# EP1K100QC208-2.net
KiCad netlist of a schematic drawn in Altium Designer
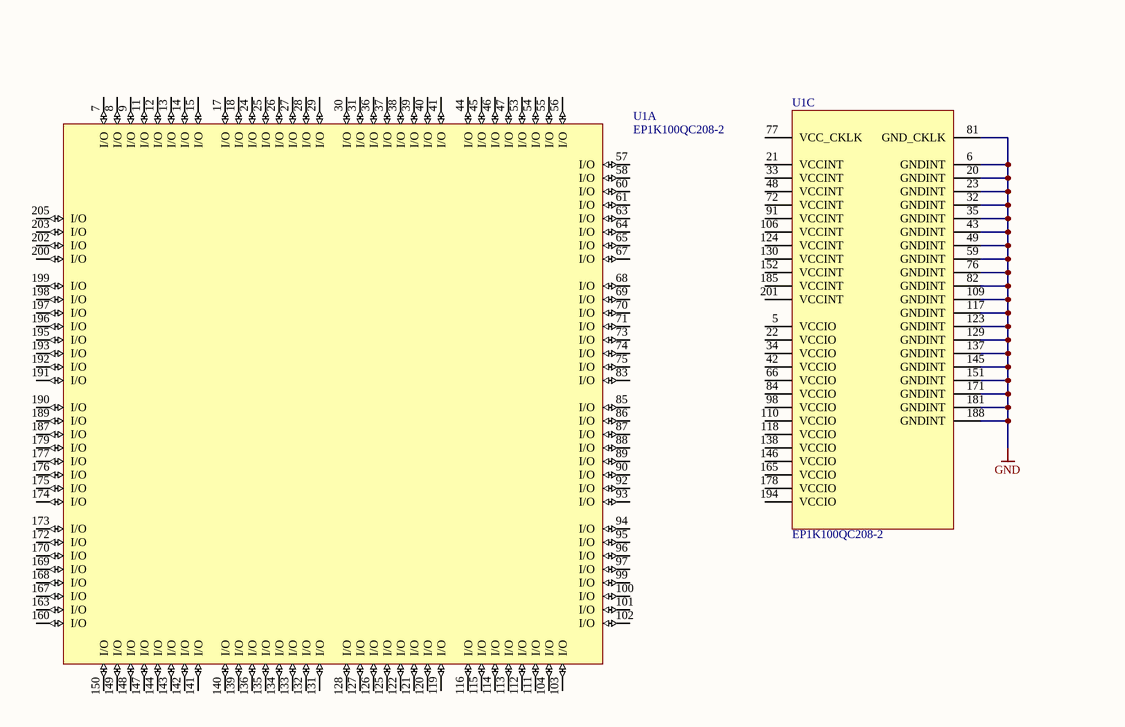
[diagram p0: EP1K100QC208-2.SchDoc, left]
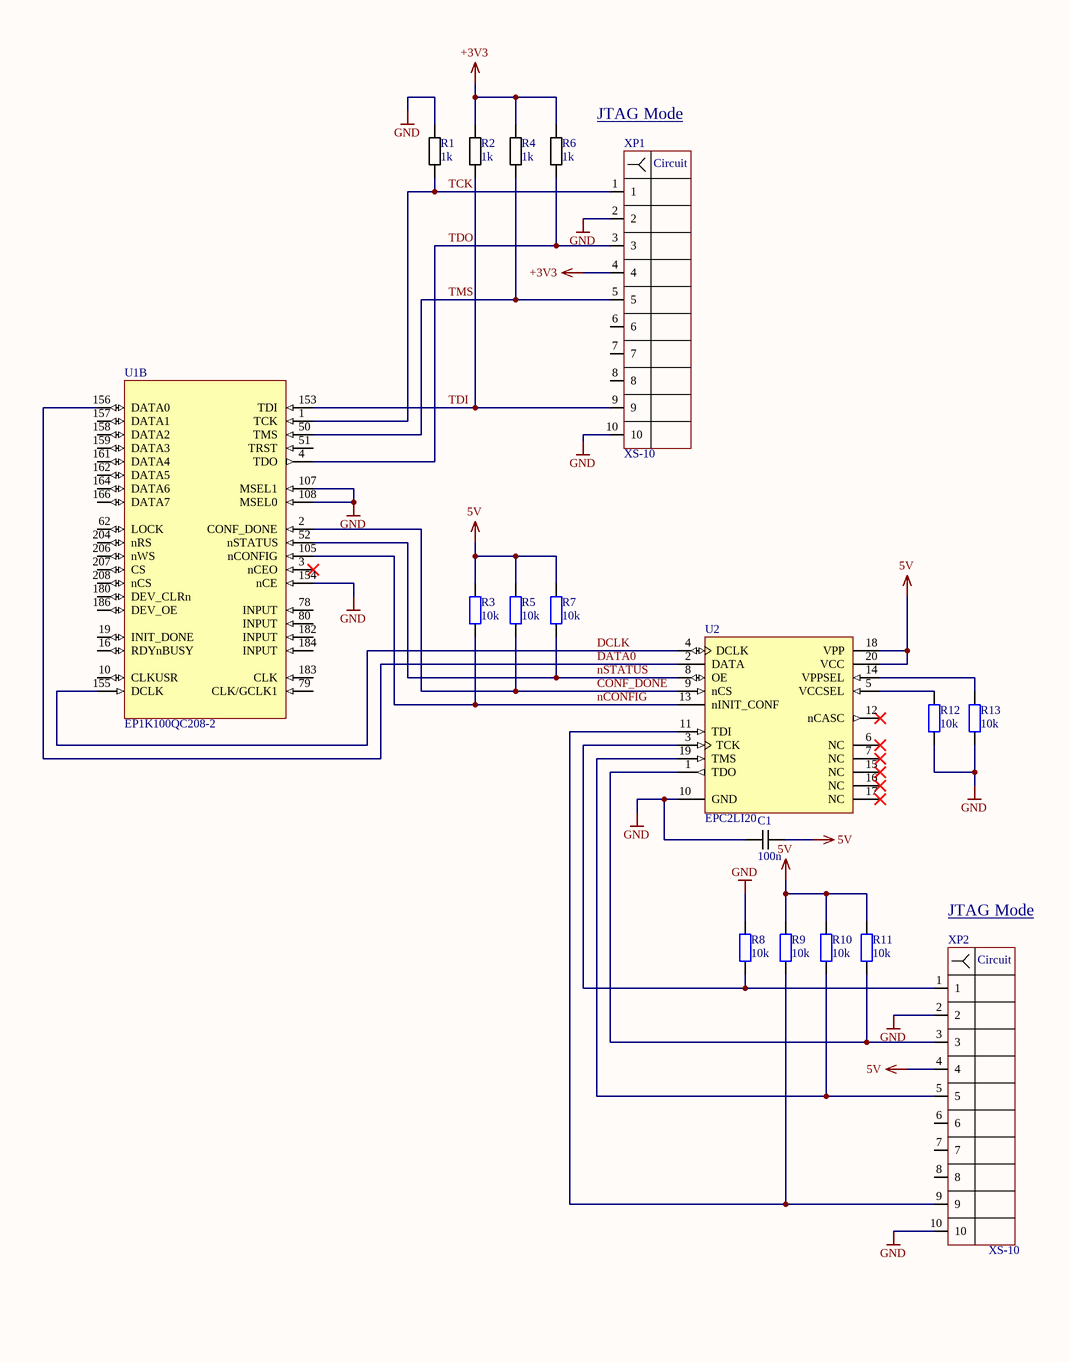
[diagram p1: EP1K100QC208-2.SchDoc, right]

(export (version "E")
  (design (tool "Eeschema 10.0.6"))
  (components
    (comp (ref "C1")
      (value "100n")
      (footprint "CAPC1608(0603)N")
      (description "?")
      (fields (field (name "PART NUMBER") "CAPC1608(0603)"))
      (libsource (lib "SssAccesDatbase") (part "Cap"))
    )
    (comp (ref "R1")
      (value "1k")
      (footprint "RESC1608(0603)N")
      (fields (field (name "PART NUMBER") "RESC1608(0603)") (field (name "DIGI-KEY PART NUMBER") "???"))
      (libsource (lib "SssAccesDatbaseDYandex") (part "Resistor general"))
    )
    (comp (ref "R2")
      (value "1k")
      (footprint "RESC1608(0603)N")
      (fields (field (name "PART NUMBER") "RESC1608(0603)") (field (name "DIGI-KEY PART NUMBER") "???"))
      (libsource (lib "SssAccesDatbaseDYandex") (part "Resistor general"))
    )
    (comp (ref "R3")
      (value "10k")
      (footprint "RESC1608(0603)N")
      (description "Resistor")
      (fields (field (name "PART NUMBER") "RESC1608(0603)") (field (name "DIGI-KEY PART NUMBER") "???"))
      (libsource (lib "ADdatabaseLibfile") (part "Res2"))
    )
    (comp (ref "R4")
      (value "1k")
      (footprint "RESC1608(0603)N")
      (fields (field (name "PART NUMBER") "RESC1608(0603)") (field (name "DIGI-KEY PART NUMBER") "???"))
      (libsource (lib "SssAccesDatbaseDYandex") (part "Resistor general"))
    )
    (comp (ref "R5")
      (value "10k")
      (footprint "RESC1608(0603)N")
      (description "Resistor")
      (fields (field (name "PART NUMBER") "RESC1608(0603)") (field (name "DIGI-KEY PART NUMBER") "???"))
      (libsource (lib "ADdatabaseLibfile") (part "Res2"))
    )
    (comp (ref "R6")
      (value "1k")
      (footprint "RESC1608(0603)N")
      (fields (field (name "PART NUMBER") "RESC1608(0603)") (field (name "DIGI-KEY PART NUMBER") "???"))
      (libsource (lib "SssAccesDatbaseDYandex") (part "Resistor general"))
    )
    (comp (ref "R7")
      (value "10k")
      (footprint "RESC1608(0603)N")
      (description "Resistor")
      (fields (field (name "PART NUMBER") "RESC1608(0603)") (field (name "DIGI-KEY PART NUMBER") "???"))
      (libsource (lib "ADdatabaseLibfile") (part "Res2"))
    )
    (comp (ref "R8")
      (value "10k")
      (footprint "RESC1608(0603)N")
      (description "Resistor")
      (fields (field (name "PART NUMBER") "RESC1608(0603)") (field (name "DIGI-KEY PART NUMBER") "???"))
      (libsource (lib "") (part "Res2_1"))
    )
    (comp (ref "R9")
      (value "10k")
      (footprint "RESC1608(0603)N")
      (description "Resistor")
      (fields (field (name "PART NUMBER") "RESC1608(0603)") (field (name "DIGI-KEY PART NUMBER") "???"))
      (libsource (lib "ADdatabaseLibfile") (part "Res2"))
    )
    (comp (ref "R10")
      (value "10k")
      (footprint "RESC1608(0603)N")
      (description "Resistor")
      (fields (field (name "PART NUMBER") "RESC1608(0603)") (field (name "DIGI-KEY PART NUMBER") "???"))
      (libsource (lib "ADdatabaseLibfile") (part "Res2"))
    )
    (comp (ref "R11")
      (value "10k")
      (footprint "RESC1608(0603)N")
      (description "Resistor")
      (fields (field (name "PART NUMBER") "RESC1608(0603)") (field (name "DIGI-KEY PART NUMBER") "???"))
      (libsource (lib "ADdatabaseLibfile") (part "Res2"))
    )
    (comp (ref "R12")
      (value "10k")
      (footprint "RESC1608(0603)N")
      (description "Resistor")
      (fields (field (name "PART NUMBER") "RESC1608(0603)") (field (name "DIGI-KEY PART NUMBER") "???"))
      (libsource (lib "ADdatabaseLibfile") (part "Res2"))
    )
    (comp (ref "R13")
      (value "10k")
      (footprint "RESC1608(0603)N")
      (description "Resistor")
      (fields (field (name "PART NUMBER") "RESC1608(0603)") (field (name "DIGI-KEY PART NUMBER") "???"))
      (libsource (lib "ADdatabaseLibfile") (part "Res2"))
    )
    (comp (ref "U1")
      (value "EP1K100QC208-2")
      (footprint "PQFP208_N")
      (fields (field (name "PUBLISHER") "Altium Limited"))
      (libsource (lib "") (part "EP1K100QC208-2_1"))
    )
    (comp (ref "U2")
      (value "EPC2LI20")
      (footprint "PLCC20_L")
      (description "IC - Ser. Config Mem Flash 1.6Mb 10 MHz")
      (fields (field (name "PUBLISHER") "Altium Limited"))
      (libsource (lib "ADdatabaseLibfile") (part "EPC2LI20"))
    )
    (comp (ref "XP1")
      (value "XS-10")
      (footprint "BH-10")
      (fields
        (field (name "PART NUMBER") "3220-10-0100-00")
        (field (name "DIGI-KEY PART NUMBER") "1175-1627-ND")
      )
      (libsource (lib "ADdatabaseLibfile") (part "XS-10"))
    )
    (comp (ref "XP2")
      (value "XS-10")
      (footprint "BH-10")
      (fields (field (name "PART NUMBER") "BH-10"))
      (libsource (lib "ADdatabaseLibfile") (part "XS-10"))
    )
  )
  (nets
    (net (code "1") (name "+3V3") (class "Default")
      (node (ref "R2") (pin "2") (pinfunction "2_2") (pintype "passive"))
      (node (ref "R4") (pin "2") (pinfunction "2_2") (pintype "passive"))
      (node (ref "R6") (pin "2") (pinfunction "2_2") (pintype "passive"))
      (node (ref "XP1") (pin "4") (pinfunction "4_4") (pintype "passive"))
    )
    (net (code "2") (name "/CONF_DONE") (class "Default")
      (node (ref "R5") (pin "2") (pinfunction "2_2") (pintype "passive"))
      (node (ref "U1") (pin "2") (pinfunction "CONF_DONE_2") (pintype "input"))
      (node (ref "U2") (pin "9") (pinfunction "nCS_9") (pintype "input"))
    )
    (net (code "3") (name "/DATA0") (class "Default")
      (node (ref "U1") (pin "156") (pinfunction "DATA0_156") (pintype "bidirectional"))
      (node (ref "U2") (pin "2") (pinfunction "DATA_2") (pintype "tri_state"))
    )
    (net (code "4") (name "/DCLK") (class "Default")
      (node (ref "U1") (pin "155") (pinfunction "DCLK_155") (pintype "input"))
      (node (ref "U2") (pin "4") (pinfunction "DCLK_4") (pintype "bidirectional"))
    )
    (net (code "5") (name "/TCK") (class "Default")
      (node (ref "R1") (pin "1") (pinfunction "1_1") (pintype "passive"))
      (node (ref "U1") (pin "1") (pinfunction "TCK_1") (pintype "input"))
      (node (ref "XP1") (pin "1") (pinfunction "1_1") (pintype "passive"))
    )
    (net (code "6") (name "/TDI") (class "Default")
      (node (ref "R2") (pin "1") (pinfunction "1_1") (pintype "passive"))
      (node (ref "U1") (pin "153") (pinfunction "TDI_153") (pintype "input"))
      (node (ref "XP1") (pin "9") (pinfunction "9_9") (pintype "passive"))
    )
    (net (code "7") (name "/TDO") (class "Default")
      (node (ref "R6") (pin "1") (pinfunction "1_1") (pintype "passive"))
      (node (ref "U1") (pin "4") (pinfunction "TDO_4") (pintype "output"))
      (node (ref "XP1") (pin "3") (pinfunction "3_3") (pintype "passive"))
    )
    (net (code "8") (name "/TMS") (class "Default")
      (node (ref "R4") (pin "1") (pinfunction "1_1") (pintype "passive"))
      (node (ref "U1") (pin "50") (pinfunction "TMS_50") (pintype "input"))
      (node (ref "XP1") (pin "5") (pinfunction "5_5") (pintype "passive"))
    )
    (net (code "9") (name "/nCONFIG") (class "Default")
      (node (ref "R3") (pin "2") (pinfunction "2_2") (pintype "passive"))
      (node (ref "U1") (pin "105") (pinfunction "nCONFIG_105") (pintype "input"))
      (node (ref "U2") (pin "13") (pinfunction "nINIT_CONF_13") (pintype "open_collector"))
    )
    (net (code "10") (name "/nSTATUS") (class "Default")
      (node (ref "R7") (pin "2") (pinfunction "2_2") (pintype "passive"))
      (node (ref "U1") (pin "52") (pinfunction "nSTATUS_52") (pintype "input"))
      (node (ref "U2") (pin "8") (pinfunction "OE_8") (pintype "bidirectional"))
    )
    (net (code "11") (name "5V") (class "Default")
      (node (ref "C1") (pin "2") (pinfunction "2_2") (pintype "passive"))
      (node (ref "R10") (pin "1") (pinfunction "1_1") (pintype "passive"))
      (node (ref "R11") (pin "1") (pinfunction "1_1") (pintype "passive"))
      (node (ref "R3") (pin "1") (pinfunction "1_1") (pintype "passive"))
      (node (ref "R5") (pin "1") (pinfunction "1_1") (pintype "passive"))
      (node (ref "R7") (pin "1") (pinfunction "1_1") (pintype "passive"))
      (node (ref "R9") (pin "1") (pinfunction "1_1") (pintype "passive"))
      (node (ref "U2") (pin "18") (pinfunction "VPP_18") (pintype "power_in"))
      (node (ref "U2") (pin "20") (pinfunction "VCC_20") (pintype "power_in"))
      (node (ref "XP2") (pin "4") (pinfunction "4_4") (pintype "passive"))
    )
    (net (code "12") (name "GND") (class "Default")
      (node (ref "C1") (pin "1") (pinfunction "1_1") (pintype "passive"))
      (node (ref "R1") (pin "2") (pinfunction "2_2") (pintype "passive"))
      (node (ref "R12") (pin "2") (pinfunction "2_2") (pintype "passive"))
      (node (ref "R13") (pin "2") (pinfunction "2_2") (pintype "passive"))
      (node (ref "R8") (pin "2") (pinfunction "2_2") (pintype "passive"))
      (node (ref "U1") (pin "107") (pinfunction "MSEL1_107") (pintype "input"))
      (node (ref "U1") (pin "108") (pinfunction "MSEL0_108") (pintype "input"))
      (node (ref "U1") (pin "109") (pinfunction "GNDINT_109") (pintype "power_in"))
      (node (ref "U1") (pin "117") (pinfunction "GNDINT_117") (pintype "power_in"))
      (node (ref "U1") (pin "123") (pinfunction "GNDINT_123") (pintype "power_in"))
      (node (ref "U1") (pin "129") (pinfunction "GNDINT_129") (pintype "power_in"))
      (node (ref "U1") (pin "137") (pinfunction "GNDINT_137") (pintype "power_in"))
      (node (ref "U1") (pin "145") (pinfunction "GNDINT_145") (pintype "power_in"))
      (node (ref "U1") (pin "151") (pinfunction "GNDINT_151") (pintype "power_in"))
      (node (ref "U1") (pin "154") (pinfunction "nCE_154") (pintype "input"))
      (node (ref "U1") (pin "171") (pinfunction "GNDINT_171") (pintype "power_in"))
      (node (ref "U1") (pin "181") (pinfunction "GNDINT_181") (pintype "power_in"))
      (node (ref "U1") (pin "188") (pinfunction "GNDINT_188") (pintype "power_in"))
      (node (ref "U1") (pin "20") (pinfunction "GNDINT_20") (pintype "power_in"))
      (node (ref "U1") (pin "23") (pinfunction "GNDINT_23") (pintype "power_in"))
      (node (ref "U1") (pin "32") (pinfunction "GNDINT_32") (pintype "power_in"))
      (node (ref "U1") (pin "35") (pinfunction "GNDINT_35") (pintype "power_in"))
      (node (ref "U1") (pin "43") (pinfunction "GNDINT_43") (pintype "power_in"))
      (node (ref "U1") (pin "49") (pinfunction "GNDINT_49") (pintype "power_in"))
      (node (ref "U1") (pin "59") (pinfunction "GNDINT_59") (pintype "power_in"))
      (node (ref "U1") (pin "6") (pinfunction "GNDINT_6") (pintype "power_in"))
      (node (ref "U1") (pin "76") (pinfunction "GNDINT_76") (pintype "power_in"))
      (node (ref "U1") (pin "81") (pinfunction "GND_CKLK_81") (pintype "power_in"))
      (node (ref "U1") (pin "82") (pinfunction "GNDINT_82") (pintype "power_in"))
      (node (ref "U2") (pin "10") (pinfunction "GND_10") (pintype "power_in"))
      (node (ref "XP1") (pin "10") (pinfunction "10_10") (pintype "passive"))
      (node (ref "XP1") (pin "2") (pinfunction "2_2") (pintype "passive"))
      (node (ref "XP2") (pin "10") (pinfunction "10_10") (pintype "passive"))
      (node (ref "XP2") (pin "2") (pinfunction "2_2") (pintype "passive"))
    )
    (net (code "13") (name "Net-(U2-TCK)") (class "Default")
      (node (ref "R8") (pin "1") (pinfunction "1_1") (pintype "passive"))
      (node (ref "U2") (pin "3") (pinfunction "TCK_3") (pintype "input"))
      (node (ref "XP2") (pin "1") (pinfunction "1_1") (pintype "passive"))
    )
    (net (code "14") (name "Net-(U2-TDI)") (class "Default")
      (node (ref "R9") (pin "2") (pinfunction "2_2") (pintype "passive"))
      (node (ref "U2") (pin "11") (pinfunction "TDI_11") (pintype "input"))
      (node (ref "XP2") (pin "9") (pinfunction "9_9") (pintype "passive"))
    )
    (net (code "15") (name "Net-(U2-TDO)") (class "Default")
      (node (ref "R11") (pin "2") (pinfunction "2_2") (pintype "passive"))
      (node (ref "U2") (pin "1") (pinfunction "TDO_1") (pintype "output"))
      (node (ref "XP2") (pin "3") (pinfunction "3_3") (pintype "passive"))
    )
    (net (code "16") (name "Net-(U2-TMS)") (class "Default")
      (node (ref "R10") (pin "2") (pinfunction "2_2") (pintype "passive"))
      (node (ref "U2") (pin "19") (pinfunction "TMS_19") (pintype "input"))
      (node (ref "XP2") (pin "5") (pinfunction "5_5") (pintype "passive"))
    )
    (net (code "17") (name "Net-(U2-VCCSEL)") (class "Default")
      (node (ref "R12") (pin "1") (pinfunction "1_1") (pintype "passive"))
      (node (ref "U2") (pin "5") (pinfunction "VCCSEL_5") (pintype "input"))
    )
    (net (code "18") (name "Net-(U2-VPPSEL)") (class "Default")
      (node (ref "R13") (pin "1") (pinfunction "1_1") (pintype "passive"))
      (node (ref "U2") (pin "14") (pinfunction "VPPSEL_14") (pintype "input"))
    )
    (net (code "19") (name "unconnected-(U1A-I{slash}O-Pad7)") (class "Default")
      (node (ref "U1") (pin "7") (pinfunction "I/O_7") (pintype "bidirectional"))
    )
    (net (code "20") (name "unconnected-(U1A-I{slash}O-Pad8)") (class "Default")
      (node (ref "U1") (pin "8") (pinfunction "I/O_8") (pintype "bidirectional"))
    )
    (net (code "21") (name "unconnected-(U1A-I{slash}O-Pad9)") (class "Default")
      (node (ref "U1") (pin "9") (pinfunction "I/O_9") (pintype "bidirectional"))
    )
    (net (code "22") (name "unconnected-(U1A-I{slash}O-Pad11)") (class "Default")
      (node (ref "U1") (pin "11") (pinfunction "I/O_11") (pintype "bidirectional"))
    )
    (net (code "23") (name "unconnected-(U1A-I{slash}O-Pad12)") (class "Default")
      (node (ref "U1") (pin "12") (pinfunction "I/O_12") (pintype "bidirectional"))
    )
    (net (code "24") (name "unconnected-(U1A-I{slash}O-Pad13)") (class "Default")
      (node (ref "U1") (pin "13") (pinfunction "I/O_13") (pintype "bidirectional"))
    )
    (net (code "25") (name "unconnected-(U1A-I{slash}O-Pad14)") (class "Default")
      (node (ref "U1") (pin "14") (pinfunction "I/O_14") (pintype "bidirectional"))
    )
    (net (code "26") (name "unconnected-(U1A-I{slash}O-Pad15)") (class "Default")
      (node (ref "U1") (pin "15") (pinfunction "I/O_15") (pintype "bidirectional"))
    )
    (net (code "27") (name "unconnected-(U1A-I{slash}O-Pad17)") (class "Default")
      (node (ref "U1") (pin "17") (pinfunction "I/O_17") (pintype "bidirectional"))
    )
    (net (code "28") (name "unconnected-(U1A-I{slash}O-Pad18)") (class "Default")
      (node (ref "U1") (pin "18") (pinfunction "I/O_18") (pintype "bidirectional"))
    )
    (net (code "29") (name "unconnected-(U1A-I{slash}O-Pad24)") (class "Default")
      (node (ref "U1") (pin "24") (pinfunction "I/O_24") (pintype "bidirectional"))
    )
    (net (code "30") (name "unconnected-(U1A-I{slash}O-Pad25)") (class "Default")
      (node (ref "U1") (pin "25") (pinfunction "I/O_25") (pintype "bidirectional"))
    )
    (net (code "31") (name "unconnected-(U1A-I{slash}O-Pad26)") (class "Default")
      (node (ref "U1") (pin "26") (pinfunction "I/O_26") (pintype "bidirectional"))
    )
    (net (code "32") (name "unconnected-(U1A-I{slash}O-Pad27)") (class "Default")
      (node (ref "U1") (pin "27") (pinfunction "I/O_27") (pintype "bidirectional"))
    )
    (net (code "33") (name "unconnected-(U1A-I{slash}O-Pad28)") (class "Default")
      (node (ref "U1") (pin "28") (pinfunction "I/O_28") (pintype "bidirectional"))
    )
    (net (code "34") (name "unconnected-(U1A-I{slash}O-Pad29)") (class "Default")
      (node (ref "U1") (pin "29") (pinfunction "I/O_29") (pintype "bidirectional"))
    )
    (net (code "35") (name "unconnected-(U1A-I{slash}O-Pad30)") (class "Default")
      (node (ref "U1") (pin "30") (pinfunction "I/O_30") (pintype "bidirectional"))
    )
    (net (code "36") (name "unconnected-(U1A-I{slash}O-Pad31)") (class "Default")
      (node (ref "U1") (pin "31") (pinfunction "I/O_31") (pintype "bidirectional"))
    )
    (net (code "37") (name "unconnected-(U1A-I{slash}O-Pad36)") (class "Default")
      (node (ref "U1") (pin "36") (pinfunction "I/O_36") (pintype "bidirectional"))
    )
    (net (code "38") (name "unconnected-(U1A-I{slash}O-Pad37)") (class "Default")
      (node (ref "U1") (pin "37") (pinfunction "I/O_37") (pintype "bidirectional"))
    )
    (net (code "39") (name "unconnected-(U1A-I{slash}O-Pad38)") (class "Default")
      (node (ref "U1") (pin "38") (pinfunction "I/O_38") (pintype "bidirectional"))
    )
    (net (code "40") (name "unconnected-(U1A-I{slash}O-Pad39)") (class "Default")
      (node (ref "U1") (pin "39") (pinfunction "I/O_39") (pintype "bidirectional"))
    )
    (net (code "41") (name "unconnected-(U1A-I{slash}O-Pad40)") (class "Default")
      (node (ref "U1") (pin "40") (pinfunction "I/O_40") (pintype "bidirectional"))
    )
    (net (code "42") (name "unconnected-(U1A-I{slash}O-Pad41)") (class "Default")
      (node (ref "U1") (pin "41") (pinfunction "I/O_41") (pintype "bidirectional"))
    )
    (net (code "43") (name "unconnected-(U1A-I{slash}O-Pad44)") (class "Default")
      (node (ref "U1") (pin "44") (pinfunction "I/O_44") (pintype "bidirectional"))
    )
    (net (code "44") (name "unconnected-(U1A-I{slash}O-Pad45)") (class "Default")
      (node (ref "U1") (pin "45") (pinfunction "I/O_45") (pintype "bidirectional"))
    )
    (net (code "45") (name "unconnected-(U1A-I{slash}O-Pad46)") (class "Default")
      (node (ref "U1") (pin "46") (pinfunction "I/O_46") (pintype "bidirectional"))
    )
    (net (code "46") (name "unconnected-(U1A-I{slash}O-Pad47)") (class "Default")
      (node (ref "U1") (pin "47") (pinfunction "I/O_47") (pintype "bidirectional"))
    )
    (net (code "47") (name "unconnected-(U1A-I{slash}O-Pad53)") (class "Default")
      (node (ref "U1") (pin "53") (pinfunction "I/O_53") (pintype "bidirectional"))
    )
    (net (code "48") (name "unconnected-(U1A-I{slash}O-Pad54)") (class "Default")
      (node (ref "U1") (pin "54") (pinfunction "I/O_54") (pintype "bidirectional"))
    )
    (net (code "49") (name "unconnected-(U1A-I{slash}O-Pad55)") (class "Default")
      (node (ref "U1") (pin "55") (pinfunction "I/O_55") (pintype "bidirectional"))
    )
    (net (code "50") (name "unconnected-(U1A-I{slash}O-Pad56)") (class "Default")
      (node (ref "U1") (pin "56") (pinfunction "I/O_56") (pintype "bidirectional"))
    )
    (net (code "51") (name "unconnected-(U1A-I{slash}O-Pad57)") (class "Default")
      (node (ref "U1") (pin "57") (pinfunction "I/O_57") (pintype "bidirectional"))
    )
    (net (code "52") (name "unconnected-(U1A-I{slash}O-Pad58)") (class "Default")
      (node (ref "U1") (pin "58") (pinfunction "I/O_58") (pintype "bidirectional"))
    )
    (net (code "53") (name "unconnected-(U1A-I{slash}O-Pad60)") (class "Default")
      (node (ref "U1") (pin "60") (pinfunction "I/O_60") (pintype "bidirectional"))
    )
    (net (code "54") (name "unconnected-(U1A-I{slash}O-Pad61)") (class "Default")
      (node (ref "U1") (pin "61") (pinfunction "I/O_61") (pintype "bidirectional"))
    )
    (net (code "55") (name "unconnected-(U1A-I{slash}O-Pad63)") (class "Default")
      (node (ref "U1") (pin "63") (pinfunction "I/O_63") (pintype "bidirectional"))
    )
    (net (code "56") (name "unconnected-(U1A-I{slash}O-Pad64)") (class "Default")
      (node (ref "U1") (pin "64") (pinfunction "I/O_64") (pintype "bidirectional"))
    )
    (net (code "57") (name "unconnected-(U1A-I{slash}O-Pad65)") (class "Default")
      (node (ref "U1") (pin "65") (pinfunction "I/O_65") (pintype "bidirectional"))
    )
    (net (code "58") (name "unconnected-(U1A-I{slash}O-Pad67)") (class "Default")
      (node (ref "U1") (pin "67") (pinfunction "I/O_67") (pintype "bidirectional"))
    )
    (net (code "59") (name "unconnected-(U1A-I{slash}O-Pad68)") (class "Default")
      (node (ref "U1") (pin "68") (pinfunction "I/O_68") (pintype "bidirectional"))
    )
    (net (code "60") (name "unconnected-(U1A-I{slash}O-Pad69)") (class "Default")
      (node (ref "U1") (pin "69") (pinfunction "I/O_69") (pintype "bidirectional"))
    )
    (net (code "61") (name "unconnected-(U1A-I{slash}O-Pad70)") (class "Default")
      (node (ref "U1") (pin "70") (pinfunction "I/O_70") (pintype "bidirectional"))
    )
    (net (code "62") (name "unconnected-(U1A-I{slash}O-Pad71)") (class "Default")
      (node (ref "U1") (pin "71") (pinfunction "I/O_71") (pintype "bidirectional"))
    )
    (net (code "63") (name "unconnected-(U1A-I{slash}O-Pad73)") (class "Default")
      (node (ref "U1") (pin "73") (pinfunction "I/O_73") (pintype "bidirectional"))
    )
    (net (code "64") (name "unconnected-(U1A-I{slash}O-Pad74)") (class "Default")
      (node (ref "U1") (pin "74") (pinfunction "I/O_74") (pintype "bidirectional"))
    )
    (net (code "65") (name "unconnected-(U1A-I{slash}O-Pad75)") (class "Default")
      (node (ref "U1") (pin "75") (pinfunction "I/O_75") (pintype "bidirectional"))
    )
    (net (code "66") (name "unconnected-(U1A-I{slash}O-Pad83)") (class "Default")
      (node (ref "U1") (pin "83") (pinfunction "I/O_83") (pintype "bidirectional"))
    )
    (net (code "67") (name "unconnected-(U1A-I{slash}O-Pad85)") (class "Default")
      (node (ref "U1") (pin "85") (pinfunction "I/O_85") (pintype "bidirectional"))
    )
    (net (code "68") (name "unconnected-(U1A-I{slash}O-Pad86)") (class "Default")
      (node (ref "U1") (pin "86") (pinfunction "I/O_86") (pintype "bidirectional"))
    )
    (net (code "69") (name "unconnected-(U1A-I{slash}O-Pad87)") (class "Default")
      (node (ref "U1") (pin "87") (pinfunction "I/O_87") (pintype "bidirectional"))
    )
    (net (code "70") (name "unconnected-(U1A-I{slash}O-Pad88)") (class "Default")
      (node (ref "U1") (pin "88") (pinfunction "I/O_88") (pintype "bidirectional"))
    )
    (net (code "71") (name "unconnected-(U1A-I{slash}O-Pad89)") (class "Default")
      (node (ref "U1") (pin "89") (pinfunction "I/O_89") (pintype "bidirectional"))
    )
    (net (code "72") (name "unconnected-(U1A-I{slash}O-Pad90)") (class "Default")
      (node (ref "U1") (pin "90") (pinfunction "I/O_90") (pintype "bidirectional"))
    )
    (net (code "73") (name "unconnected-(U1A-I{slash}O-Pad92)") (class "Default")
      (node (ref "U1") (pin "92") (pinfunction "I/O_92") (pintype "bidirectional"))
    )
    (net (code "74") (name "unconnected-(U1A-I{slash}O-Pad93)") (class "Default")
      (node (ref "U1") (pin "93") (pinfunction "I/O_93") (pintype "bidirectional"))
    )
    (net (code "75") (name "unconnected-(U1A-I{slash}O-Pad94)") (class "Default")
      (node (ref "U1") (pin "94") (pinfunction "I/O_94") (pintype "bidirectional"))
    )
    (net (code "76") (name "unconnected-(U1A-I{slash}O-Pad95)") (class "Default")
      (node (ref "U1") (pin "95") (pinfunction "I/O_95") (pintype "bidirectional"))
    )
    (net (code "77") (name "unconnected-(U1A-I{slash}O-Pad96)") (class "Default")
      (node (ref "U1") (pin "96") (pinfunction "I/O_96") (pintype "bidirectional"))
    )
    (net (code "78") (name "unconnected-(U1A-I{slash}O-Pad97)") (class "Default")
      (node (ref "U1") (pin "97") (pinfunction "I/O_97") (pintype "bidirectional"))
    )
    (net (code "79") (name "unconnected-(U1A-I{slash}O-Pad99)") (class "Default")
      (node (ref "U1") (pin "99") (pinfunction "I/O_99") (pintype "bidirectional"))
    )
    (net (code "80") (name "unconnected-(U1A-I{slash}O-Pad100)") (class "Default")
      (node (ref "U1") (pin "100") (pinfunction "I/O_100") (pintype "bidirectional"))
    )
    (net (code "81") (name "unconnected-(U1A-I{slash}O-Pad101)") (class "Default")
      (node (ref "U1") (pin "101") (pinfunction "I/O_101") (pintype "bidirectional"))
    )
    (net (code "82") (name "unconnected-(U1A-I{slash}O-Pad102)") (class "Default")
      (node (ref "U1") (pin "102") (pinfunction "I/O_102") (pintype "bidirectional"))
    )
    (net (code "83") (name "unconnected-(U1A-I{slash}O-Pad103)") (class "Default")
      (node (ref "U1") (pin "103") (pinfunction "I/O_103") (pintype "bidirectional"))
    )
    (net (code "84") (name "unconnected-(U1A-I{slash}O-Pad104)") (class "Default")
      (node (ref "U1") (pin "104") (pinfunction "I/O_104") (pintype "bidirectional"))
    )
    (net (code "85") (name "unconnected-(U1A-I{slash}O-Pad111)") (class "Default")
      (node (ref "U1") (pin "111") (pinfunction "I/O_111") (pintype "bidirectional"))
    )
    (net (code "86") (name "unconnected-(U1A-I{slash}O-Pad112)") (class "Default")
      (node (ref "U1") (pin "112") (pinfunction "I/O_112") (pintype "bidirectional"))
    )
    (net (code "87") (name "unconnected-(U1A-I{slash}O-Pad113)") (class "Default")
      (node (ref "U1") (pin "113") (pinfunction "I/O_113") (pintype "bidirectional"))
    )
    (net (code "88") (name "unconnected-(U1A-I{slash}O-Pad114)") (class "Default")
      (node (ref "U1") (pin "114") (pinfunction "I/O_114") (pintype "bidirectional"))
    )
    (net (code "89") (name "unconnected-(U1A-I{slash}O-Pad115)") (class "Default")
      (node (ref "U1") (pin "115") (pinfunction "I/O_115") (pintype "bidirectional"))
    )
    (net (code "90") (name "unconnected-(U1A-I{slash}O-Pad116)") (class "Default")
      (node (ref "U1") (pin "116") (pinfunction "I/O_116") (pintype "bidirectional"))
    )
    (net (code "91") (name "unconnected-(U1A-I{slash}O-Pad119)") (class "Default")
      (node (ref "U1") (pin "119") (pinfunction "I/O_119") (pintype "bidirectional"))
    )
    (net (code "92") (name "unconnected-(U1A-I{slash}O-Pad120)") (class "Default")
      (node (ref "U1") (pin "120") (pinfunction "I/O_120") (pintype "bidirectional"))
    )
    (net (code "93") (name "unconnected-(U1A-I{slash}O-Pad121)") (class "Default")
      (node (ref "U1") (pin "121") (pinfunction "I/O_121") (pintype "bidirectional"))
    )
    (net (code "94") (name "unconnected-(U1A-I{slash}O-Pad122)") (class "Default")
      (node (ref "U1") (pin "122") (pinfunction "I/O_122") (pintype "bidirectional"))
    )
    (net (code "95") (name "unconnected-(U1A-I{slash}O-Pad125)") (class "Default")
      (node (ref "U1") (pin "125") (pinfunction "I/O_125") (pintype "bidirectional"))
    )
    (net (code "96") (name "unconnected-(U1A-I{slash}O-Pad126)") (class "Default")
      (node (ref "U1") (pin "126") (pinfunction "I/O_126") (pintype "bidirectional"))
    )
    (net (code "97") (name "unconnected-(U1A-I{slash}O-Pad127)") (class "Default")
      (node (ref "U1") (pin "127") (pinfunction "I/O_127") (pintype "bidirectional"))
    )
    (net (code "98") (name "unconnected-(U1A-I{slash}O-Pad128)") (class "Default")
      (node (ref "U1") (pin "128") (pinfunction "I/O_128") (pintype "bidirectional"))
    )
    (net (code "99") (name "unconnected-(U1A-I{slash}O-Pad131)") (class "Default")
      (node (ref "U1") (pin "131") (pinfunction "I/O_131") (pintype "bidirectional"))
    )
    (net (code "100") (name "unconnected-(U1A-I{slash}O-Pad132)") (class "Default")
      (node (ref "U1") (pin "132") (pinfunction "I/O_132") (pintype "bidirectional"))
    )
    (net (code "101") (name "unconnected-(U1A-I{slash}O-Pad133)") (class "Default")
      (node (ref "U1") (pin "133") (pinfunction "I/O_133") (pintype "bidirectional"))
    )
    (net (code "102") (name "unconnected-(U1A-I{slash}O-Pad134)") (class "Default")
      (node (ref "U1") (pin "134") (pinfunction "I/O_134") (pintype "bidirectional"))
    )
    (net (code "103") (name "unconnected-(U1A-I{slash}O-Pad135)") (class "Default")
      (node (ref "U1") (pin "135") (pinfunction "I/O_135") (pintype "bidirectional"))
    )
    (net (code "104") (name "unconnected-(U1A-I{slash}O-Pad136)") (class "Default")
      (node (ref "U1") (pin "136") (pinfunction "I/O_136") (pintype "bidirectional"))
    )
    (net (code "105") (name "unconnected-(U1A-I{slash}O-Pad139)") (class "Default")
      (node (ref "U1") (pin "139") (pinfunction "I/O_139") (pintype "bidirectional"))
    )
    (net (code "106") (name "unconnected-(U1A-I{slash}O-Pad140)") (class "Default")
      (node (ref "U1") (pin "140") (pinfunction "I/O_140") (pintype "bidirectional"))
    )
    (net (code "107") (name "unconnected-(U1A-I{slash}O-Pad141)") (class "Default")
      (node (ref "U1") (pin "141") (pinfunction "I/O_141") (pintype "bidirectional"))
    )
    (net (code "108") (name "unconnected-(U1A-I{slash}O-Pad142)") (class "Default")
      (node (ref "U1") (pin "142") (pinfunction "I/O_142") (pintype "bidirectional"))
    )
    (net (code "109") (name "unconnected-(U1A-I{slash}O-Pad143)") (class "Default")
      (node (ref "U1") (pin "143") (pinfunction "I/O_143") (pintype "bidirectional"))
    )
    (net (code "110") (name "unconnected-(U1A-I{slash}O-Pad144)") (class "Default")
      (node (ref "U1") (pin "144") (pinfunction "I/O_144") (pintype "bidirectional"))
    )
    (net (code "111") (name "unconnected-(U1A-I{slash}O-Pad147)") (class "Default")
      (node (ref "U1") (pin "147") (pinfunction "I/O_147") (pintype "bidirectional"))
    )
    (net (code "112") (name "unconnected-(U1A-I{slash}O-Pad148)") (class "Default")
      (node (ref "U1") (pin "148") (pinfunction "I/O_148") (pintype "bidirectional"))
    )
    (net (code "113") (name "unconnected-(U1A-I{slash}O-Pad149)") (class "Default")
      (node (ref "U1") (pin "149") (pinfunction "I/O_149") (pintype "bidirectional"))
    )
    (net (code "114") (name "unconnected-(U1A-I{slash}O-Pad150)") (class "Default")
      (node (ref "U1") (pin "150") (pinfunction "I/O_150") (pintype "bidirectional"))
    )
    (net (code "115") (name "unconnected-(U1A-I{slash}O-Pad160)") (class "Default")
      (node (ref "U1") (pin "160") (pinfunction "I/O_160") (pintype "bidirectional"))
    )
    (net (code "116") (name "unconnected-(U1A-I{slash}O-Pad163)") (class "Default")
      (node (ref "U1") (pin "163") (pinfunction "I/O_163") (pintype "bidirectional"))
    )
    (net (code "117") (name "unconnected-(U1A-I{slash}O-Pad167)") (class "Default")
      (node (ref "U1") (pin "167") (pinfunction "I/O_167") (pintype "bidirectional"))
    )
    (net (code "118") (name "unconnected-(U1A-I{slash}O-Pad168)") (class "Default")
      (node (ref "U1") (pin "168") (pinfunction "I/O_168") (pintype "bidirectional"))
    )
    (net (code "119") (name "unconnected-(U1A-I{slash}O-Pad169)") (class "Default")
      (node (ref "U1") (pin "169") (pinfunction "I/O_169") (pintype "bidirectional"))
    )
    (net (code "120") (name "unconnected-(U1A-I{slash}O-Pad170)") (class "Default")
      (node (ref "U1") (pin "170") (pinfunction "I/O_170") (pintype "bidirectional"))
    )
    (net (code "121") (name "unconnected-(U1A-I{slash}O-Pad172)") (class "Default")
      (node (ref "U1") (pin "172") (pinfunction "I/O_172") (pintype "bidirectional"))
    )
    (net (code "122") (name "unconnected-(U1A-I{slash}O-Pad173)") (class "Default")
      (node (ref "U1") (pin "173") (pinfunction "I/O_173") (pintype "bidirectional"))
    )
    (net (code "123") (name "unconnected-(U1A-I{slash}O-Pad174)") (class "Default")
      (node (ref "U1") (pin "174") (pinfunction "I/O_174") (pintype "bidirectional"))
    )
    (net (code "124") (name "unconnected-(U1A-I{slash}O-Pad175)") (class "Default")
      (node (ref "U1") (pin "175") (pinfunction "I/O_175") (pintype "bidirectional"))
    )
    (net (code "125") (name "unconnected-(U1A-I{slash}O-Pad176)") (class "Default")
      (node (ref "U1") (pin "176") (pinfunction "I/O_176") (pintype "bidirectional"))
    )
    (net (code "126") (name "unconnected-(U1A-I{slash}O-Pad177)") (class "Default")
      (node (ref "U1") (pin "177") (pinfunction "I/O_177") (pintype "bidirectional"))
    )
    (net (code "127") (name "unconnected-(U1A-I{slash}O-Pad179)") (class "Default")
      (node (ref "U1") (pin "179") (pinfunction "I/O_179") (pintype "bidirectional"))
    )
    (net (code "128") (name "unconnected-(U1A-I{slash}O-Pad187)") (class "Default")
      (node (ref "U1") (pin "187") (pinfunction "I/O_187") (pintype "bidirectional"))
    )
    (net (code "129") (name "unconnected-(U1A-I{slash}O-Pad189)") (class "Default")
      (node (ref "U1") (pin "189") (pinfunction "I/O_189") (pintype "bidirectional"))
    )
    (net (code "130") (name "unconnected-(U1A-I{slash}O-Pad190)") (class "Default")
      (node (ref "U1") (pin "190") (pinfunction "I/O_190") (pintype "bidirectional"))
    )
    (net (code "131") (name "unconnected-(U1A-I{slash}O-Pad191)") (class "Default")
      (node (ref "U1") (pin "191") (pinfunction "I/O_191") (pintype "bidirectional"))
    )
    (net (code "132") (name "unconnected-(U1A-I{slash}O-Pad192)") (class "Default")
      (node (ref "U1") (pin "192") (pinfunction "I/O_192") (pintype "bidirectional"))
    )
    (net (code "133") (name "unconnected-(U1A-I{slash}O-Pad193)") (class "Default")
      (node (ref "U1") (pin "193") (pinfunction "I/O_193") (pintype "bidirectional"))
    )
    (net (code "134") (name "unconnected-(U1A-I{slash}O-Pad195)") (class "Default")
      (node (ref "U1") (pin "195") (pinfunction "I/O_195") (pintype "bidirectional"))
    )
    (net (code "135") (name "unconnected-(U1A-I{slash}O-Pad196)") (class "Default")
      (node (ref "U1") (pin "196") (pinfunction "I/O_196") (pintype "bidirectional"))
    )
    (net (code "136") (name "unconnected-(U1A-I{slash}O-Pad197)") (class "Default")
      (node (ref "U1") (pin "197") (pinfunction "I/O_197") (pintype "bidirectional"))
    )
    (net (code "137") (name "unconnected-(U1A-I{slash}O-Pad198)") (class "Default")
      (node (ref "U1") (pin "198") (pinfunction "I/O_198") (pintype "bidirectional"))
    )
    (net (code "138") (name "unconnected-(U1A-I{slash}O-Pad199)") (class "Default")
      (node (ref "U1") (pin "199") (pinfunction "I/O_199") (pintype "bidirectional"))
    )
    (net (code "139") (name "unconnected-(U1A-I{slash}O-Pad200)") (class "Default")
      (node (ref "U1") (pin "200") (pinfunction "I/O_200") (pintype "bidirectional"))
    )
    (net (code "140") (name "unconnected-(U1A-I{slash}O-Pad202)") (class "Default")
      (node (ref "U1") (pin "202") (pinfunction "I/O_202") (pintype "bidirectional"))
    )
    (net (code "141") (name "unconnected-(U1A-I{slash}O-Pad203)") (class "Default")
      (node (ref "U1") (pin "203") (pinfunction "I/O_203") (pintype "bidirectional"))
    )
    (net (code "142") (name "unconnected-(U1A-I{slash}O-Pad205)") (class "Default")
      (node (ref "U1") (pin "205") (pinfunction "I/O_205") (pintype "bidirectional"))
    )
    (net (code "143") (name "unconnected-(U1B-CLK-Pad183)") (class "Default")
      (node (ref "U1") (pin "183") (pinfunction "CLK_183") (pintype "input"))
    )
    (net (code "144") (name "unconnected-(U1B-CLKUSR-Pad10)") (class "Default")
      (node (ref "U1") (pin "10") (pinfunction "CLKUSR_10") (pintype "bidirectional"))
    )
    (net (code "145") (name "unconnected-(U1B-CLK{slash}GCLK1-Pad79)") (class "Default")
      (node (ref "U1") (pin "79") (pinfunction "CLK/GCLK1_79") (pintype "input"))
    )
    (net (code "146") (name "unconnected-(U1B-CS-Pad207)") (class "Default")
      (node (ref "U1") (pin "207") (pinfunction "CS_207") (pintype "bidirectional"))
    )
    (net (code "147") (name "unconnected-(U1B-DATA1-Pad157)") (class "Default")
      (node (ref "U1") (pin "157") (pinfunction "DATA1_157") (pintype "bidirectional"))
    )
    (net (code "148") (name "unconnected-(U1B-DATA2-Pad158)") (class "Default")
      (node (ref "U1") (pin "158") (pinfunction "DATA2_158") (pintype "bidirectional"))
    )
    (net (code "149") (name "unconnected-(U1B-DATA3-Pad159)") (class "Default")
      (node (ref "U1") (pin "159") (pinfunction "DATA3_159") (pintype "bidirectional"))
    )
    (net (code "150") (name "unconnected-(U1B-DATA4-Pad161)") (class "Default")
      (node (ref "U1") (pin "161") (pinfunction "DATA4_161") (pintype "bidirectional"))
    )
    (net (code "151") (name "unconnected-(U1B-DATA5-Pad162)") (class "Default")
      (node (ref "U1") (pin "162") (pinfunction "DATA5_162") (pintype "bidirectional"))
    )
    (net (code "152") (name "unconnected-(U1B-DATA6-Pad164)") (class "Default")
      (node (ref "U1") (pin "164") (pinfunction "DATA6_164") (pintype "bidirectional"))
    )
    (net (code "153") (name "unconnected-(U1B-DATA7-Pad166)") (class "Default")
      (node (ref "U1") (pin "166") (pinfunction "DATA7_166") (pintype "bidirectional"))
    )
    (net (code "154") (name "unconnected-(U1B-DEV_CLRn-Pad180)") (class "Default")
      (node (ref "U1") (pin "180") (pinfunction "DEV_CLRn_180") (pintype "bidirectional"))
    )
    (net (code "155") (name "unconnected-(U1B-DEV_OE-Pad186)") (class "Default")
      (node (ref "U1") (pin "186") (pinfunction "DEV_OE_186") (pintype "bidirectional"))
    )
    (net (code "156") (name "unconnected-(U1B-INIT_DONE-Pad19)") (class "Default")
      (node (ref "U1") (pin "19") (pinfunction "INIT_DONE_19") (pintype "bidirectional"))
    )
    (net (code "157") (name "unconnected-(U1B-INPUT-Pad78)") (class "Default")
      (node (ref "U1") (pin "78") (pinfunction "INPUT_78") (pintype "input"))
    )
    (net (code "158") (name "unconnected-(U1B-INPUT-Pad80)") (class "Default")
      (node (ref "U1") (pin "80") (pinfunction "INPUT_80") (pintype "input"))
    )
    (net (code "159") (name "unconnected-(U1B-INPUT-Pad182)") (class "Default")
      (node (ref "U1") (pin "182") (pinfunction "INPUT_182") (pintype "input"))
    )
    (net (code "160") (name "unconnected-(U1B-INPUT-Pad184)") (class "Default")
      (node (ref "U1") (pin "184") (pinfunction "INPUT_184") (pintype "input"))
    )
    (net (code "161") (name "unconnected-(U1B-LOCK-Pad62)") (class "Default")
      (node (ref "U1") (pin "62") (pinfunction "LOCK_62") (pintype "bidirectional"))
    )
    (net (code "162") (name "unconnected-(U1B-RDYnBUSY-Pad16)") (class "Default")
      (node (ref "U1") (pin "16") (pinfunction "RDYnBUSY_16") (pintype "bidirectional"))
    )
    (net (code "163") (name "unconnected-(U1B-TRST-Pad51)") (class "Default")
      (node (ref "U1") (pin "51") (pinfunction "TRST_51") (pintype "input"))
    )
    (net (code "164") (name "unconnected-(U1B-nCEO-Pad3)") (class "Default")
      (node (ref "U1") (pin "3") (pinfunction "nCEO_3") (pintype "input+no_connect"))
    )
    (net (code "165") (name "unconnected-(U1B-nCS-Pad208)") (class "Default")
      (node (ref "U1") (pin "208") (pinfunction "nCS_208") (pintype "bidirectional"))
    )
    (net (code "166") (name "unconnected-(U1B-nRS-Pad204)") (class "Default")
      (node (ref "U1") (pin "204") (pinfunction "nRS_204") (pintype "bidirectional"))
    )
    (net (code "167") (name "unconnected-(U1B-nWS-Pad206)") (class "Default")
      (node (ref "U1") (pin "206") (pinfunction "nWS_206") (pintype "bidirectional"))
    )
    (net (code "168") (name "unconnected-(U1C-VCCINT-Pad21)") (class "Default")
      (node (ref "U1") (pin "21") (pinfunction "VCCINT_21") (pintype "power_in"))
    )
    (net (code "169") (name "unconnected-(U1C-VCCINT-Pad33)") (class "Default")
      (node (ref "U1") (pin "33") (pinfunction "VCCINT_33") (pintype "power_in"))
    )
    (net (code "170") (name "unconnected-(U1C-VCCINT-Pad48)") (class "Default")
      (node (ref "U1") (pin "48") (pinfunction "VCCINT_48") (pintype "power_in"))
    )
    (net (code "171") (name "unconnected-(U1C-VCCINT-Pad72)") (class "Default")
      (node (ref "U1") (pin "72") (pinfunction "VCCINT_72") (pintype "power_in"))
    )
    (net (code "172") (name "unconnected-(U1C-VCCINT-Pad91)") (class "Default")
      (node (ref "U1") (pin "91") (pinfunction "VCCINT_91") (pintype "power_in"))
    )
    (net (code "173") (name "unconnected-(U1C-VCCINT-Pad106)") (class "Default")
      (node (ref "U1") (pin "106") (pinfunction "VCCINT_106") (pintype "power_in"))
    )
    (net (code "174") (name "unconnected-(U1C-VCCINT-Pad124)") (class "Default")
      (node (ref "U1") (pin "124") (pinfunction "VCCINT_124") (pintype "power_in"))
    )
    (net (code "175") (name "unconnected-(U1C-VCCINT-Pad130)") (class "Default")
      (node (ref "U1") (pin "130") (pinfunction "VCCINT_130") (pintype "power_in"))
    )
    (net (code "176") (name "unconnected-(U1C-VCCINT-Pad152)") (class "Default")
      (node (ref "U1") (pin "152") (pinfunction "VCCINT_152") (pintype "power_in"))
    )
    (net (code "177") (name "unconnected-(U1C-VCCINT-Pad185)") (class "Default")
      (node (ref "U1") (pin "185") (pinfunction "VCCINT_185") (pintype "power_in"))
    )
    (net (code "178") (name "unconnected-(U1C-VCCINT-Pad201)") (class "Default")
      (node (ref "U1") (pin "201") (pinfunction "VCCINT_201") (pintype "power_in"))
    )
    (net (code "179") (name "unconnected-(U1C-VCCIO-Pad5)") (class "Default")
      (node (ref "U1") (pin "5") (pinfunction "VCCIO_5") (pintype "power_in"))
    )
    (net (code "180") (name "unconnected-(U1C-VCCIO-Pad22)") (class "Default")
      (node (ref "U1") (pin "22") (pinfunction "VCCIO_22") (pintype "power_in"))
    )
    (net (code "181") (name "unconnected-(U1C-VCCIO-Pad34)") (class "Default")
      (node (ref "U1") (pin "34") (pinfunction "VCCIO_34") (pintype "power_in"))
    )
    (net (code "182") (name "unconnected-(U1C-VCCIO-Pad42)") (class "Default")
      (node (ref "U1") (pin "42") (pinfunction "VCCIO_42") (pintype "power_in"))
    )
    (net (code "183") (name "unconnected-(U1C-VCCIO-Pad66)") (class "Default")
      (node (ref "U1") (pin "66") (pinfunction "VCCIO_66") (pintype "power_in"))
    )
    (net (code "184") (name "unconnected-(U1C-VCCIO-Pad84)") (class "Default")
      (node (ref "U1") (pin "84") (pinfunction "VCCIO_84") (pintype "power_in"))
    )
    (net (code "185") (name "unconnected-(U1C-VCCIO-Pad98)") (class "Default")
      (node (ref "U1") (pin "98") (pinfunction "VCCIO_98") (pintype "power_in"))
    )
    (net (code "186") (name "unconnected-(U1C-VCCIO-Pad110)") (class "Default")
      (node (ref "U1") (pin "110") (pinfunction "VCCIO_110") (pintype "power_in"))
    )
    (net (code "187") (name "unconnected-(U1C-VCCIO-Pad118)") (class "Default")
      (node (ref "U1") (pin "118") (pinfunction "VCCIO_118") (pintype "power_in"))
    )
    (net (code "188") (name "unconnected-(U1C-VCCIO-Pad138)") (class "Default")
      (node (ref "U1") (pin "138") (pinfunction "VCCIO_138") (pintype "power_in"))
    )
    (net (code "189") (name "unconnected-(U1C-VCCIO-Pad146)") (class "Default")
      (node (ref "U1") (pin "146") (pinfunction "VCCIO_146") (pintype "power_in"))
    )
    (net (code "190") (name "unconnected-(U1C-VCCIO-Pad165)") (class "Default")
      (node (ref "U1") (pin "165") (pinfunction "VCCIO_165") (pintype "power_in"))
    )
    (net (code "191") (name "unconnected-(U1C-VCCIO-Pad178)") (class "Default")
      (node (ref "U1") (pin "178") (pinfunction "VCCIO_178") (pintype "power_in"))
    )
    (net (code "192") (name "unconnected-(U1C-VCCIO-Pad194)") (class "Default")
      (node (ref "U1") (pin "194") (pinfunction "VCCIO_194") (pintype "power_in"))
    )
    (net (code "193") (name "unconnected-(U1C-VCC_CKLK-Pad77)") (class "Default")
      (node (ref "U1") (pin "77") (pinfunction "VCC_CKLK_77") (pintype "power_in"))
    )
    (net (code "194") (name "unconnected-(U2-NC-Pad6)") (class "Default")
      (node (ref "U2") (pin "6") (pinfunction "NC_6") (pintype "passive+no_connect"))
    )
    (net (code "195") (name "unconnected-(U2-NC-Pad7)") (class "Default")
      (node (ref "U2") (pin "7") (pinfunction "NC_7") (pintype "passive+no_connect"))
    )
    (net (code "196") (name "unconnected-(U2-NC-Pad15)") (class "Default")
      (node (ref "U2") (pin "15") (pinfunction "NC_15") (pintype "passive+no_connect"))
    )
    (net (code "197") (name "unconnected-(U2-NC-Pad16)") (class "Default")
      (node (ref "U2") (pin "16") (pinfunction "NC_16") (pintype "passive+no_connect"))
    )
    (net (code "198") (name "unconnected-(U2-NC-Pad17)") (class "Default")
      (node (ref "U2") (pin "17") (pinfunction "NC_17") (pintype "passive+no_connect"))
    )
    (net (code "199") (name "unconnected-(U2-nCASC-Pad12)") (class "Default")
      (node (ref "U2") (pin "12") (pinfunction "nCASC_12") (pintype "output+no_connect"))
    )
    (net (code "200") (name "unconnected-(XP1-Pad6)") (class "Default")
      (node (ref "XP1") (pin "6") (pinfunction "6_6") (pintype "passive"))
    )
    (net (code "201") (name "unconnected-(XP1-Pad7)") (class "Default")
      (node (ref "XP1") (pin "7") (pinfunction "7_7") (pintype "passive"))
    )
    (net (code "202") (name "unconnected-(XP1-Pad8)") (class "Default")
      (node (ref "XP1") (pin "8") (pinfunction "8_8") (pintype "passive"))
    )
    (net (code "203") (name "unconnected-(XP2-Pad6)") (class "Default")
      (node (ref "XP2") (pin "6") (pinfunction "6_6") (pintype "passive"))
    )
    (net (code "204") (name "unconnected-(XP2-Pad7)") (class "Default")
      (node (ref "XP2") (pin "7") (pinfunction "7_7") (pintype "passive"))
    )
    (net (code "205") (name "unconnected-(XP2-Pad8)") (class "Default")
      (node (ref "XP2") (pin "8") (pinfunction "8_8") (pintype "passive"))
    )
  )
)
